# Design.net
KiCad netlist of a schematic drawn in Altium Designer
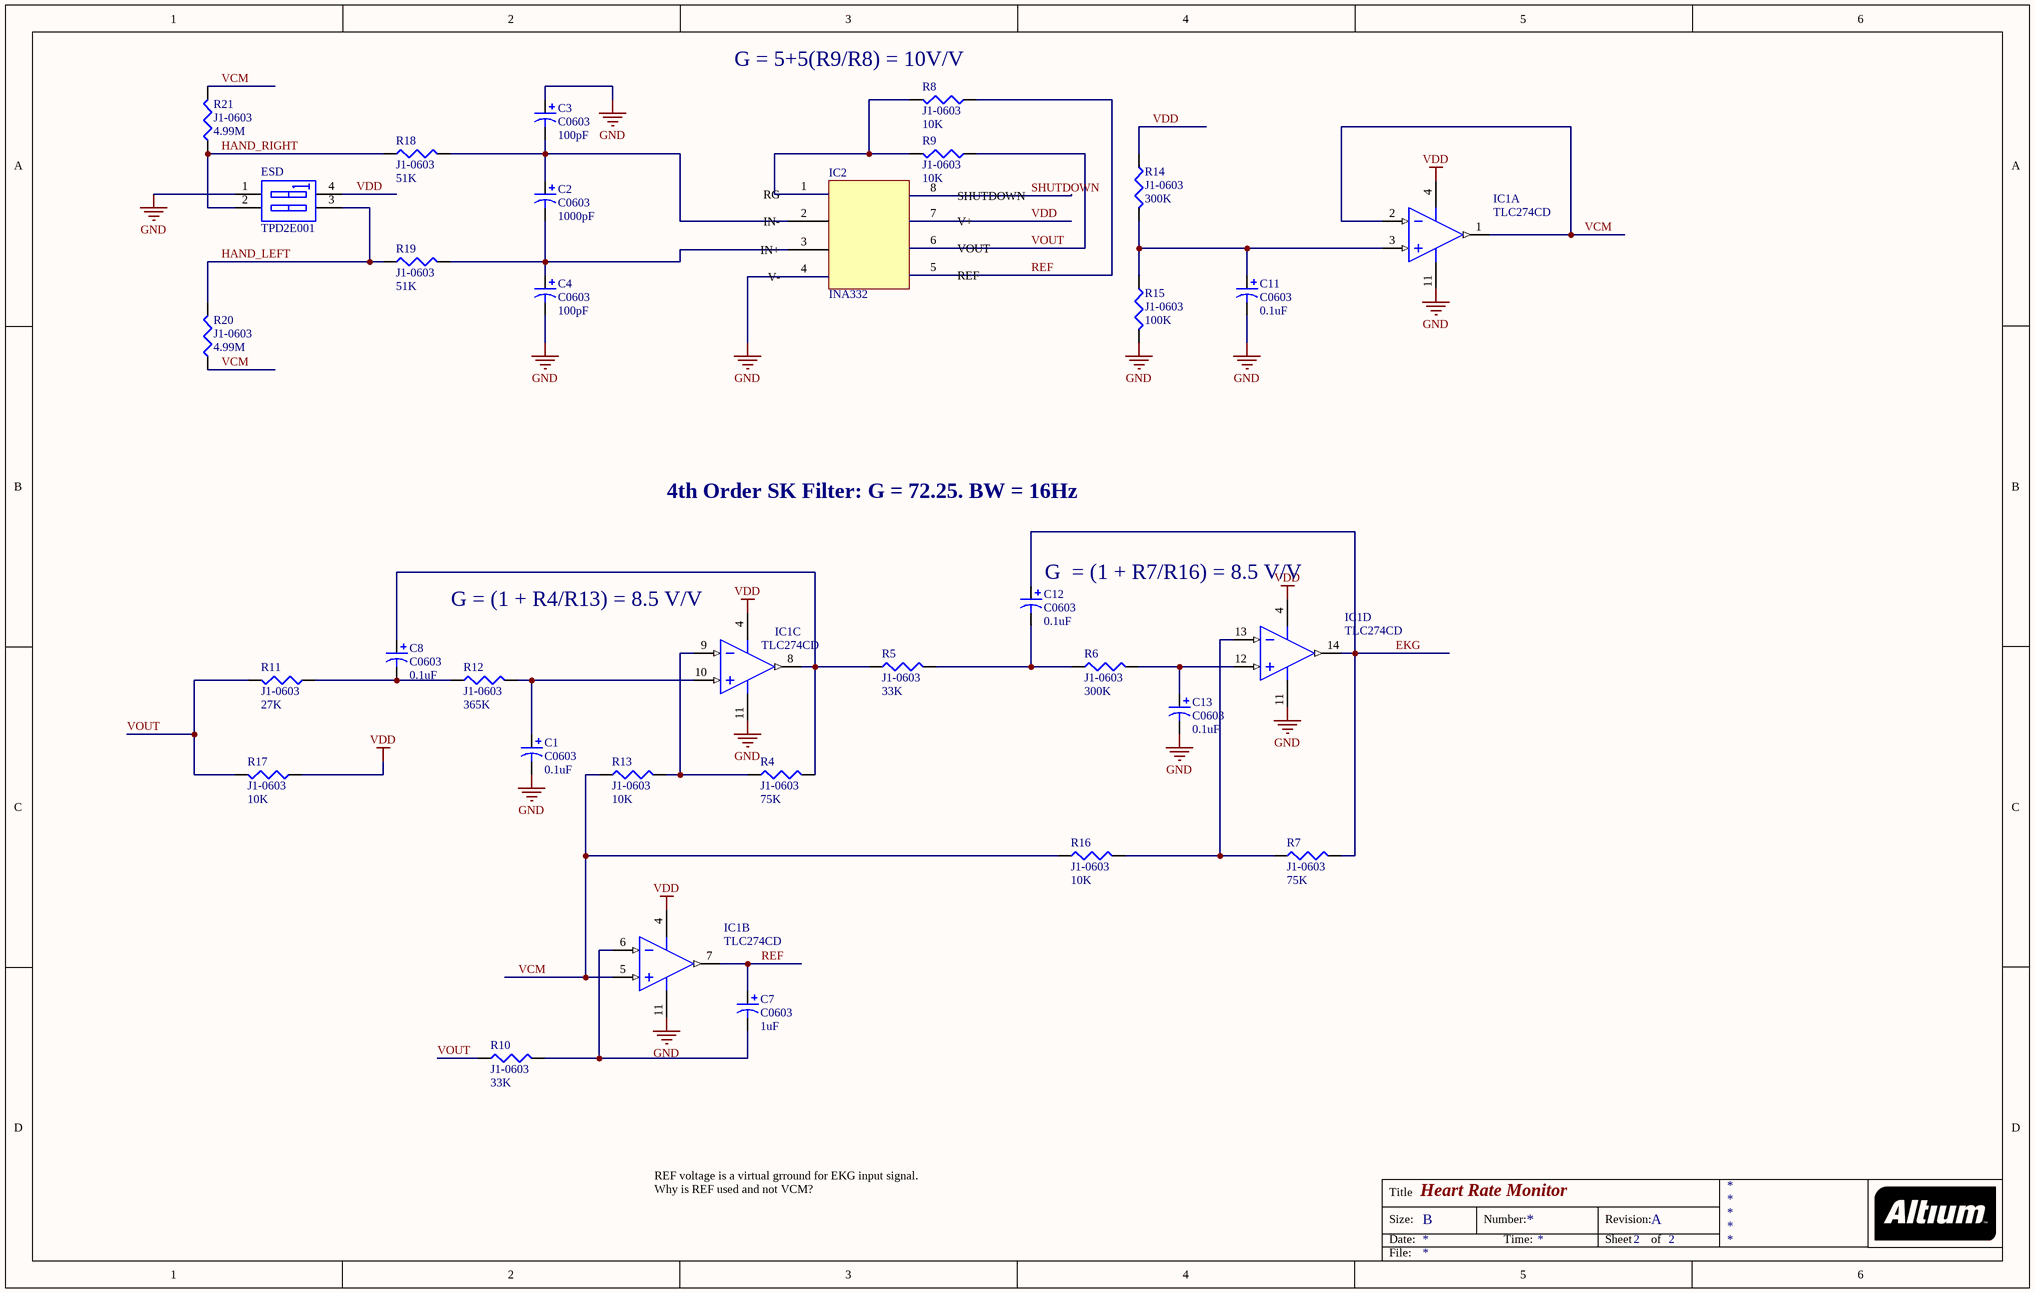
[diagram p0: Design.SchDoc]

(export (version "E")
  (design (tool "Eeschema 10.0.6"))
  (components
    (comp (ref "C1")
      (value "C0603")
      (footprint "RESC0603N")
      (description "Polarized Capacitor (Surface Mount)")
      (fields (field (name "ALTIUM_VALUE") "0.1uF") (field (name "PUBLISHER") "Altium Limited"))
      (libsource (lib "Miscellaneous Devices") (part "Cap Pol3"))
    )
    (comp (ref "C2")
      (value "C0603")
      (footprint "RESC0603N")
      (description "Polarized Capacitor (Surface Mount)")
      (fields (field (name "ALTIUM_VALUE") "1000pF") (field (name "PUBLISHER") "Altium Limited"))
      (libsource (lib "Miscellaneous Devices") (part "Cap Pol3"))
    )
    (comp (ref "C3")
      (value "C0603")
      (footprint "RESC0603N")
      (description "Polarized Capacitor (Surface Mount)")
      (fields (field (name "ALTIUM_VALUE") "100pF") (field (name "PUBLISHER") "Altium Limited"))
      (libsource (lib "Miscellaneous Devices") (part "Cap Pol3"))
    )
    (comp (ref "C4")
      (value "C0603")
      (footprint "RESC0603N")
      (description "Polarized Capacitor (Surface Mount)")
      (fields (field (name "ALTIUM_VALUE") "100pF") (field (name "PUBLISHER") "Altium Limited"))
      (libsource (lib "Miscellaneous Devices") (part "Cap Pol3"))
    )
    (comp (ref "C7")
      (value "C0603")
      (footprint "RESC0603N")
      (description "Polarized Capacitor (Surface Mount)")
      (fields (field (name "ALTIUM_VALUE") "1uF") (field (name "PUBLISHER") "Altium Limited"))
      (libsource (lib "Miscellaneous Devices") (part "Cap Pol3"))
    )
    (comp (ref "C8")
      (value "C0603")
      (footprint "RESC0603N")
      (description "Polarized Capacitor (Surface Mount)")
      (fields (field (name "ALTIUM_VALUE") "0.1uF") (field (name "PUBLISHER") "Altium Limited"))
      (libsource (lib "Miscellaneous Devices") (part "Cap Pol3"))
    )
    (comp (ref "C11")
      (value "C0603")
      (footprint "RESC0603N")
      (description "Polarized Capacitor (Surface Mount)")
      (fields (field (name "ALTIUM_VALUE") "0.1uF") (field (name "PUBLISHER") "Altium Limited"))
      (libsource (lib "Miscellaneous Devices") (part "Cap Pol3"))
    )
    (comp (ref "C12")
      (value "C0603")
      (footprint "RESC0603N")
      (description "Polarized Capacitor (Surface Mount)")
      (fields (field (name "ALTIUM_VALUE") "0.1uF") (field (name "PUBLISHER") "Altium Limited"))
      (libsource (lib "Miscellaneous Devices") (part "Cap Pol3"))
    )
    (comp (ref "C13")
      (value "C0603")
      (footprint "RESC0603N")
      (description "Polarized Capacitor (Surface Mount)")
      (fields (field (name "ALTIUM_VALUE") "0.1uF") (field (name "PUBLISHER") "Altium Limited"))
      (libsource (lib "Miscellaneous Devices") (part "Cap Pol3"))
    )
    (comp (ref "ESD")
      (value "TPD2E001")
      (footprint "SOT143N")
      (description "DIP Switch, 2 Position, SPST")
      (fields (field (name "PUBLISHER") "Altium Limited"))
      (libsource (lib "Miscellaneous Devices") (part "SW DIP-2"))
    )
    (comp (ref "IC1")
      (value "TLC274CD")
      (footprint "D014_N")
      (description "LinCMOS Precision Quad Operational Amplifier")
      (fields (field (name "PUBLISHER") "Altium Limited"))
      (libsource (lib "TI Operational Amplifier") (part "TLC274CD"))
    )
    (comp (ref "IC2")
      (value "INA332")
      (footprint "TSOP65P490-8AN")
      (description "Instrumentation Amp MSOP-8")
      (libsource (lib "Schematic Components") (part "INA332"))
    )
    (comp (ref "R4")
      (value "J1-0603")
      (footprint "RESC0603N")
      (description "Resistor")
      (fields (field (name "ALTIUM_VALUE") "75K") (field (name "PUBLISHER") "Altium Limited"))
      (libsource (lib "Miscellaneous Devices") (part "Res3"))
    )
    (comp (ref "R5")
      (value "J1-0603")
      (footprint "RESC0603N")
      (description "Resistor")
      (fields (field (name "ALTIUM_VALUE") "33K") (field (name "PUBLISHER") "Altium Limited"))
      (libsource (lib "Miscellaneous Devices") (part "Res3"))
    )
    (comp (ref "R6")
      (value "J1-0603")
      (footprint "RESC0603N")
      (description "Resistor")
      (fields (field (name "ALTIUM_VALUE") "300K") (field (name "PUBLISHER") "Altium Limited"))
      (libsource (lib "Miscellaneous Devices") (part "Res3"))
    )
    (comp (ref "R7")
      (value "J1-0603")
      (footprint "RESC0603N")
      (description "Resistor")
      (fields (field (name "ALTIUM_VALUE") "75K") (field (name "PUBLISHER") "Altium Limited"))
      (libsource (lib "Miscellaneous Devices") (part "Res3"))
    )
    (comp (ref "R8")
      (value "J1-0603")
      (footprint "RESC0603N")
      (description "Resistor")
      (fields (field (name "ALTIUM_VALUE") "10K") (field (name "PUBLISHER") "Altium Limited"))
      (libsource (lib "Miscellaneous Devices") (part "Res3"))
    )
    (comp (ref "R9")
      (value "J1-0603")
      (footprint "RESC0603N")
      (description "Resistor")
      (fields (field (name "ALTIUM_VALUE") "10K") (field (name "PUBLISHER") "Altium Limited"))
      (libsource (lib "Miscellaneous Devices") (part "Res3"))
    )
    (comp (ref "R10")
      (value "J1-0603")
      (footprint "RESC0603N")
      (description "Resistor")
      (fields (field (name "ALTIUM_VALUE") "33K") (field (name "PUBLISHER") "Altium Limited"))
      (libsource (lib "Miscellaneous Devices") (part "Res3"))
    )
    (comp (ref "R11")
      (value "J1-0603")
      (footprint "RESC0603N")
      (description "Resistor")
      (fields (field (name "ALTIUM_VALUE") "27K") (field (name "PUBLISHER") "Altium Limited"))
      (libsource (lib "Miscellaneous Devices") (part "Res3"))
    )
    (comp (ref "R12")
      (value "J1-0603")
      (footprint "RESC0603N")
      (description "Resistor")
      (fields (field (name "ALTIUM_VALUE") "365K") (field (name "PUBLISHER") "Altium Limited"))
      (libsource (lib "Miscellaneous Devices") (part "Res3"))
    )
    (comp (ref "R13")
      (value "J1-0603")
      (footprint "RESC0603N")
      (description "Resistor")
      (fields (field (name "ALTIUM_VALUE") "10K") (field (name "PUBLISHER") "Altium Limited"))
      (libsource (lib "Miscellaneous Devices") (part "Res3"))
    )
    (comp (ref "R14")
      (value "J1-0603")
      (footprint "RESC0603N")
      (description "Resistor")
      (fields (field (name "ALTIUM_VALUE") "300K") (field (name "PUBLISHER") "Altium Limited"))
      (libsource (lib "Miscellaneous Devices") (part "Res3"))
    )
    (comp (ref "R15")
      (value "J1-0603")
      (footprint "RESC0603N")
      (description "Resistor")
      (fields (field (name "ALTIUM_VALUE") "100K") (field (name "PUBLISHER") "Altium Limited"))
      (libsource (lib "Miscellaneous Devices") (part "Res3"))
    )
    (comp (ref "R16")
      (value "J1-0603")
      (footprint "RESC0603N")
      (description "Resistor")
      (fields (field (name "ALTIUM_VALUE") "10K") (field (name "PUBLISHER") "Altium Limited"))
      (libsource (lib "Miscellaneous Devices") (part "Res3"))
    )
    (comp (ref "R17")
      (value "J1-0603")
      (footprint "RESC0603N")
      (description "Resistor")
      (fields (field (name "ALTIUM_VALUE") "10K") (field (name "PUBLISHER") "Altium Limited"))
      (libsource (lib "Miscellaneous Devices") (part "Res3"))
    )
    (comp (ref "R18")
      (value "J1-0603")
      (footprint "RESC0603N")
      (description "Resistor")
      (fields (field (name "ALTIUM_VALUE") "51K") (field (name "PUBLISHER") "Altium Limited"))
      (libsource (lib "Miscellaneous Devices") (part "Res3"))
    )
    (comp (ref "R19")
      (value "J1-0603")
      (footprint "RESC0603N")
      (description "Resistor")
      (fields (field (name "ALTIUM_VALUE") "51K") (field (name "PUBLISHER") "Altium Limited"))
      (libsource (lib "Miscellaneous Devices") (part "Res3"))
    )
    (comp (ref "R20")
      (value "J1-0603")
      (footprint "RESC0603N")
      (description "Resistor")
      (fields (field (name "ALTIUM_VALUE") "4.99M") (field (name "PUBLISHER") "Altium Limited"))
      (libsource (lib "Miscellaneous Devices") (part "Res3"))
    )
    (comp (ref "R21")
      (value "J1-0603")
      (footprint "RESC0603N")
      (description "Resistor")
      (fields (field (name "ALTIUM_VALUE") "4.99M") (field (name "PUBLISHER") "Altium Limited"))
      (libsource (lib "Miscellaneous Devices") (part "=PackageReference"))
    )
  )
  (nets
    (net (code "1") (name "/EKG") (class "Default")
      (node (ref "C12") (pin "1") (pinfunction "1_1") (pintype "passive"))
      (node (ref "IC1") (pin "14") (pinfunction "OUT_14") (pintype "output"))
      (node (ref "R7") (pin "2") (pinfunction "2_2") (pintype "passive"))
    )
    (net (code "2") (name "/HAND_LEFT") (class "Default")
      (node (ref "ESD") (pin "3") (pinfunction "B2_3") (pintype "passive"))
      (node (ref "R19") (pin "1") (pinfunction "1_1") (pintype "passive"))
      (node (ref "R20") (pin "2") (pinfunction "2_2") (pintype "passive"))
    )
    (net (code "3") (name "/HAND_RIGHT") (class "Default")
      (node (ref "ESD") (pin "2") (pinfunction "A2_2") (pintype "passive"))
      (node (ref "R18") (pin "1") (pinfunction "1_1") (pintype "passive"))
      (node (ref "R21") (pin "1") (pinfunction "1_1") (pintype "passive"))
    )
    (net (code "4") (name "/REF") (class "Default")
      (node (ref "C7") (pin "1") (pinfunction "1_1") (pintype "passive"))
      (node (ref "IC1") (pin "7") (pinfunction "OUT_7") (pintype "output"))
      (node (ref "IC2") (pin "5") (pinfunction "REF_5") (pintype "passive"))
      (node (ref "R8") (pin "1") (pinfunction "1_1") (pintype "passive"))
    )
    (net (code "5") (name "/SHUTDOWN") (class "Default")
      (node (ref "IC2") (pin "8") (pinfunction "SHUTDOWN_8") (pintype "passive"))
    )
    (net (code "6") (name "/VCM") (class "Default")
      (node (ref "IC1") (pin "1") (pinfunction "OUT_1") (pintype "output"))
      (node (ref "IC1") (pin "2") (pinfunction "IN-_2") (pintype "input"))
      (node (ref "IC1") (pin "5") (pinfunction "IN+_5") (pintype "input"))
      (node (ref "R13") (pin "1") (pinfunction "1_1") (pintype "passive"))
      (node (ref "R16") (pin "1") (pinfunction "1_1") (pintype "passive"))
      (node (ref "R20") (pin "1") (pinfunction "1_1") (pintype "passive"))
      (node (ref "R21") (pin "2") (pinfunction "2_2") (pintype "passive"))
    )
    (net (code "7") (name "/VOUT") (class "Default")
      (node (ref "IC2") (pin "6") (pinfunction "VOUT_6") (pintype "passive"))
      (node (ref "R10") (pin "1") (pinfunction "1_1") (pintype "passive"))
      (node (ref "R11") (pin "2") (pinfunction "2_2") (pintype "passive"))
      (node (ref "R17") (pin "2") (pinfunction "2_2") (pintype "passive"))
      (node (ref "R9") (pin "1") (pinfunction "1_1") (pintype "passive"))
    )
    (net (code "8") (name "GND") (class "Default")
      (node (ref "C1") (pin "2") (pinfunction "2_2") (pintype "passive"))
      (node (ref "C11") (pin "2") (pinfunction "2_2") (pintype "passive"))
      (node (ref "C13") (pin "2") (pinfunction "2_2") (pintype "passive"))
      (node (ref "C3") (pin "1") (pinfunction "1_1") (pintype "passive"))
      (node (ref "C4") (pin "2") (pinfunction "2_2") (pintype "passive"))
      (node (ref "ESD") (pin "1") (pinfunction "A1_1") (pintype "passive"))
      (node (ref "IC1") (pin "11") (pinfunction "V-_11") (pintype "power_in"))
      (node (ref "IC2") (pin "4") (pinfunction "V-_4") (pintype "passive"))
      (node (ref "R15") (pin "2") (pinfunction "2_2") (pintype "passive"))
    )
    (net (code "9") (name "Net-(C8-Pad2)") (class "Default")
      (node (ref "C8") (pin "2") (pinfunction "2_2") (pintype "passive"))
      (node (ref "R11") (pin "1") (pinfunction "1_1") (pintype "passive"))
      (node (ref "R12") (pin "1") (pinfunction "1_1") (pintype "passive"))
    )
    (net (code "10") (name "Net-(C12-Pad2)") (class "Default")
      (node (ref "C12") (pin "2") (pinfunction "2_2") (pintype "passive"))
      (node (ref "R5") (pin "2") (pinfunction "2_2") (pintype "passive"))
      (node (ref "R6") (pin "1") (pinfunction "1_1") (pintype "passive"))
    )
    (net (code "11") (name "Net-(IC1A-IN+)") (class "Default")
      (node (ref "C11") (pin "1") (pinfunction "1_1") (pintype "passive"))
      (node (ref "IC1") (pin "3") (pinfunction "IN+_3") (pintype "input"))
      (node (ref "R14") (pin "2") (pinfunction "2_2") (pintype "passive"))
      (node (ref "R15") (pin "1") (pinfunction "1_1") (pintype "passive"))
    )
    (net (code "12") (name "Net-(IC1B-IN-)") (class "Default")
      (node (ref "C7") (pin "2") (pinfunction "2_2") (pintype "passive"))
      (node (ref "IC1") (pin "6") (pinfunction "IN-_6") (pintype "input"))
      (node (ref "R10") (pin "2") (pinfunction "2_2") (pintype "passive"))
    )
    (net (code "13") (name "Net-(IC1C-IN+)") (class "Default")
      (node (ref "C1") (pin "1") (pinfunction "1_1") (pintype "passive"))
      (node (ref "IC1") (pin "10") (pinfunction "IN+_10") (pintype "input"))
      (node (ref "R12") (pin "2") (pinfunction "2_2") (pintype "passive"))
    )
    (net (code "14") (name "Net-(IC1C-IN-)") (class "Default")
      (node (ref "IC1") (pin "9") (pinfunction "IN-_9") (pintype "input"))
      (node (ref "R13") (pin "2") (pinfunction "2_2") (pintype "passive"))
      (node (ref "R4") (pin "1") (pinfunction "1_1") (pintype "passive"))
    )
    (net (code "15") (name "Net-(IC1C-OUT)") (class "Default")
      (node (ref "C8") (pin "1") (pinfunction "1_1") (pintype "passive"))
      (node (ref "IC1") (pin "8") (pinfunction "OUT_8") (pintype "output"))
      (node (ref "R4") (pin "2") (pinfunction "2_2") (pintype "passive"))
      (node (ref "R5") (pin "1") (pinfunction "1_1") (pintype "passive"))
    )
    (net (code "16") (name "Net-(IC1D-IN+)") (class "Default")
      (node (ref "C13") (pin "1") (pinfunction "1_1") (pintype "passive"))
      (node (ref "IC1") (pin "12") (pinfunction "IN+_12") (pintype "input"))
      (node (ref "R6") (pin "2") (pinfunction "2_2") (pintype "passive"))
    )
    (net (code "17") (name "Net-(IC1D-IN-)") (class "Default")
      (node (ref "IC1") (pin "13") (pinfunction "IN-_13") (pintype "input"))
      (node (ref "R16") (pin "2") (pinfunction "2_2") (pintype "passive"))
      (node (ref "R7") (pin "1") (pinfunction "1_1") (pintype "passive"))
    )
    (net (code "18") (name "Net-(IC2-IN+)") (class "Default")
      (node (ref "C2") (pin "2") (pinfunction "2_2") (pintype "passive"))
      (node (ref "C4") (pin "1") (pinfunction "1_1") (pintype "passive"))
      (node (ref "IC2") (pin "3") (pinfunction "IN+_3") (pintype "passive"))
      (node (ref "R19") (pin "2") (pinfunction "2_2") (pintype "passive"))
    )
    (net (code "19") (name "Net-(IC2-IN-)") (class "Default")
      (node (ref "C2") (pin "1") (pinfunction "1_1") (pintype "passive"))
      (node (ref "C3") (pin "2") (pinfunction "2_2") (pintype "passive"))
      (node (ref "IC2") (pin "2") (pinfunction "IN-_2") (pintype "passive"))
      (node (ref "R18") (pin "2") (pinfunction "2_2") (pintype "passive"))
    )
    (net (code "20") (name "Net-(IC2-RG)") (class "Default")
      (node (ref "IC2") (pin "1") (pinfunction "RG_1") (pintype "passive"))
      (node (ref "R8") (pin "2") (pinfunction "2_2") (pintype "passive"))
      (node (ref "R9") (pin "2") (pinfunction "2_2") (pintype "passive"))
    )
    (net (code "21") (name "VDD") (class "Default")
      (node (ref "ESD") (pin "4") (pinfunction "B1_4") (pintype "passive"))
      (node (ref "IC1") (pin "4") (pinfunction "V+_4") (pintype "power_in"))
      (node (ref "IC2") (pin "7") (pinfunction "V+_7") (pintype "passive"))
      (node (ref "R14") (pin "1") (pinfunction "1_1") (pintype "passive"))
      (node (ref "R17") (pin "1") (pinfunction "1_1") (pintype "passive"))
    )
  )
)
